# 8_-_Voltage_Conversions_Delays.net
KiCad netlist of a schematic drawn in Altium Designer
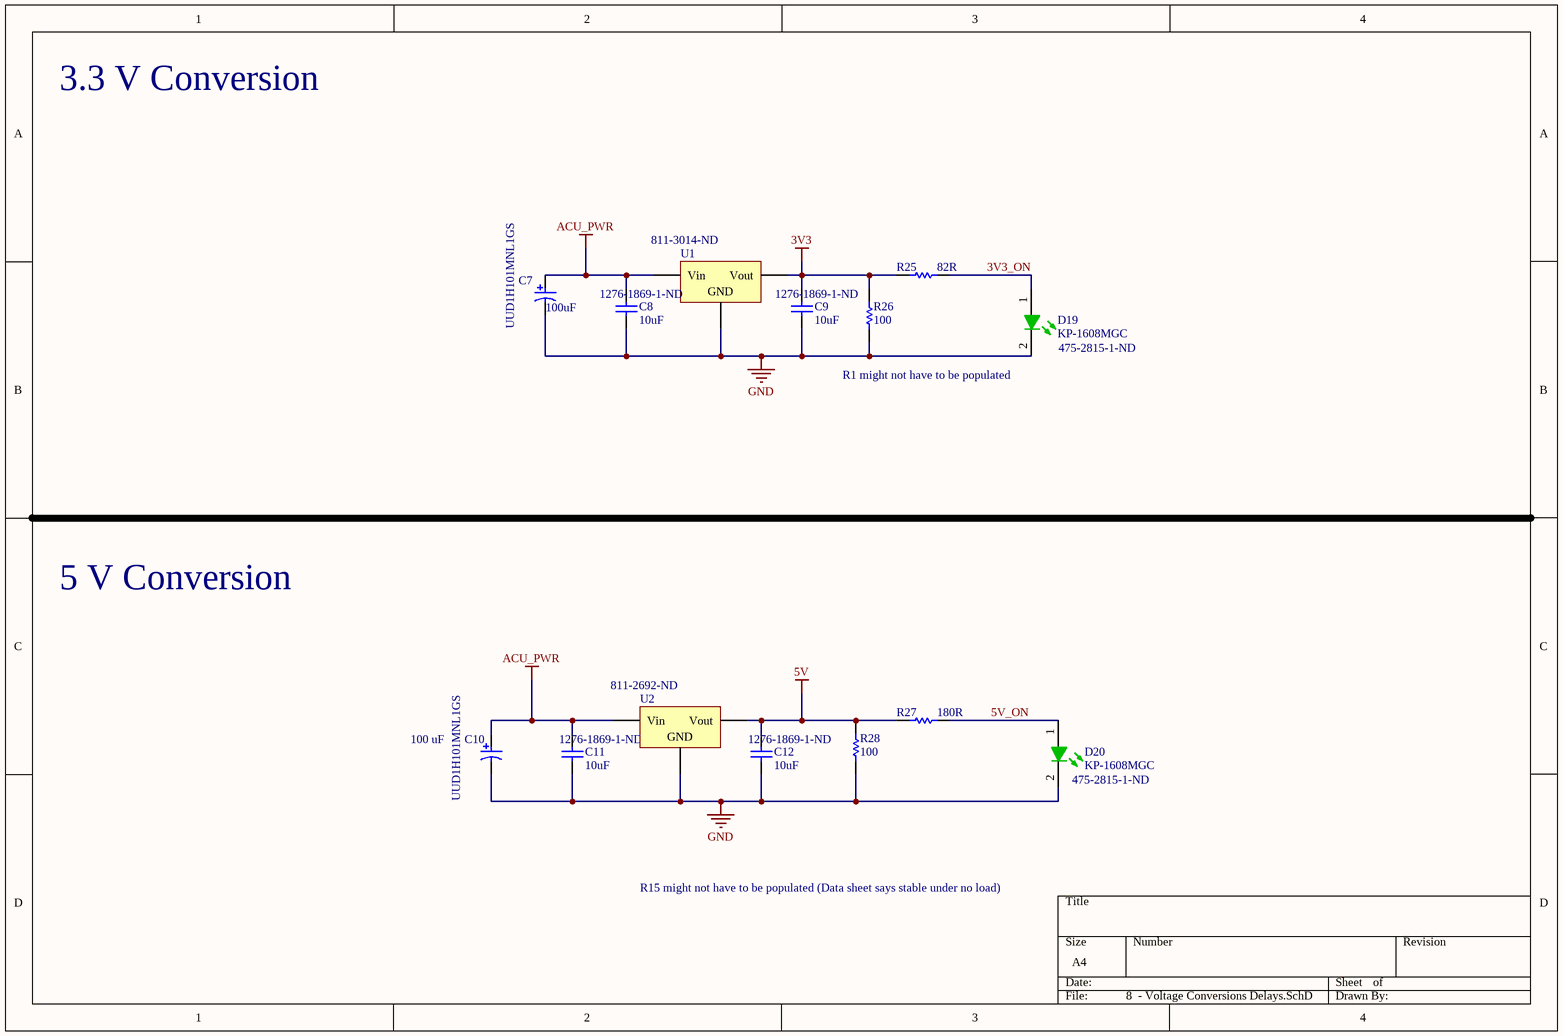
[diagram p0: 8  - Voltage Conversions Delays.SchDoc]

(export (version "E")
  (design (tool "Eeschema 10.0.6"))
  (components
    (comp (ref "C7")
      (value "UUD1H101MNL1GS")
      (footprint "NIC-CAPA2-8X10_V")
      (fields (field (name "MANUFACTURER") "Nichicon") (field (name "TOLERANCE") "±20%"))
      (libsource (lib "Altium Content Vault") (part "CMP-0687-00073-1"))
    )
    (comp (ref "C8")
      (value "10uF")
      (footprint "0603R-generic")
      (description "Capacitor")
      (fields
        (field (name "MANUFACTURER") "Yageo")
        (field (name "MANUFACTURER PART NUMBER") "CC1210ZKY5V8BB106")
        (field (name "SUPPLIER PART NUMBER 2") "1276-1869-1-ND")
      )
      (libsource (lib "Miscellaneous Devices") (part "Cap"))
    )
    (comp (ref "C9")
      (value "10uF")
      (footprint "0603R-generic")
      (description "Capacitor")
      (fields
        (field (name "MANUFACTURER") "Yageo")
        (field (name "MANUFACTURER PART NUMBER") "CC1210ZKY5V8BB106")
        (field (name "SUPPLIER PART NUMBER 2") "1276-1869-1-ND")
      )
      (libsource (lib "Miscellaneous Devices") (part "Cap"))
    )
    (comp (ref "C10")
      (value "UUD1H101MNL1GS")
      (footprint "NIC-CAPA2-8X10_V")
      (fields
        (field (name "MANUFACTURER") "Nichicon")
        (field (name "RATED CAPACITANCE") "100 uF")
        (field (name "TOLERANCE") "±20%")
      )
      (libsource (lib "Altium Content Vault") (part "CMP-0687-00073-1"))
    )
    (comp (ref "C11")
      (value "10uF")
      (footprint "0603R-generic")
      (description "Capacitor")
      (fields
        (field (name "MANUFACTURER") "Yageo")
        (field (name "MANUFACTURER PART NUMBER") "CC1210ZKY5V8BB106")
        (field (name "SUPPLIER PART NUMBER 2") "1276-1869-1-ND")
      )
      (libsource (lib "Miscellaneous Devices") (part "Cap"))
    )
    (comp (ref "C12")
      (value "10uF")
      (footprint "0603R-generic")
      (description "Capacitor")
      (fields
        (field (name "MANUFACTURER") "Yageo")
        (field (name "MANUFACTURER PART NUMBER") "CC1210ZKY5V8BB106")
        (field (name "SUPPLIER PART NUMBER 2") "1276-1869-1-ND")
      )
      (libsource (lib "Miscellaneous Devices") (part "Cap"))
    )
    (comp (ref "D19")
      (value "KP-1608MGC")
      (footprint "KING-0603LED_GREEN_V")
      (description "LED, SMT, 0603(1608), 1.1mm thickness, Green")
      (fields
        (field (name "MANUFACTURER") "Kingbright")
        (field (name "SUPPLIER PART NUMBER 1") "475-2815-1-ND")
      )
      (libsource (lib "Altium Content Vault") (part "KING-LED-GREEN-A1K2-2"))
    )
    (comp (ref "D20")
      (value "KP-1608MGC")
      (footprint "KING-0603LED_GREEN_V")
      (description "LED, SMT, 0603(1608), 1.1mm thickness, Green")
      (fields
        (field (name "MANUFACTURER") "Kingbright")
        (field (name "SUPPLIER PART NUMBER 1") "475-2815-1-ND")
      )
      (libsource (lib "Altium Content Vault") (part "KING-LED-GREEN-A1K2-2"))
    )
    (comp (ref "R25")
      (value "82R")
      (footprint "1608[0603]")
      (description "Resistor")
      (fields
        (field (name "MANUFACTURER") "Yageo")
        (field (name "MANUFACTURER PART NUMBER") "RC0603JR-0782RL")
      )
      (libsource (lib "Miscellaneous Devices") (part "Res1"))
    )
    (comp (ref "R26")
      (value "100")
      (footprint "1608[0603]")
      (description "Resistor")
      (fields
        (field (name "MANUFACTURER") "Yageo")
        (field (name "MANUFACTURER PART NUMBER") "RC0603JR-0782RL")
      )
      (libsource (lib "Miscellaneous Devices") (part "Res1"))
    )
    (comp (ref "R27")
      (value "180R")
      (footprint "1608[0603]")
      (description "Resistor")
      (fields
        (field (name "MANUFACTURER") "Yageo")
        (field (name "MANUFACTURER PART NUMBER") "RC0603JR-07180RL")
      )
      (libsource (lib "Miscellaneous Devices") (part "Res1"))
    )
    (comp (ref "R28")
      (value "100")
      (footprint "1608[0603]")
      (description "Resistor")
      (fields
        (field (name "MANUFACTURER") "Yageo")
        (field (name "MANUFACTURER PART NUMBER") "RC0603JR-0782RL")
      )
      (libsource (lib "Miscellaneous Devices") (part "Res1"))
    )
    (comp (ref "U1")
      (value "Volt Reg")
      (footprint "DCDC_VERTICAL")
      (description "Voltage Regulator")
      (fields
        (field (name "SUPPLIER PART NUMBER 1") "811-3014-ND")
        (field (name "PUBLISHER") "Altium Limited")
      )
      (libsource (lib "Miscellaneous Devices") (part "Volt Reg"))
    )
    (comp (ref "U2")
      (value "Volt Reg")
      (footprint "DCDC_HORIZONTAL")
      (description "Voltage Regulator")
      (fields
        (field (name "SUPPLIER PART NUMBER 1") "811-2692-ND")
        (field (name "PUBLISHER") "Altium Limited")
      )
      (libsource (lib "Miscellaneous Devices") (part "Volt Reg"))
    )
  )
  (nets
    (net (code "1") (name "/3V3_ON") (class "Default")
      (node (ref "D19") (pin "1") (pinfunction "A_1") (pintype "passive"))
      (node (ref "R25") (pin "2") (pinfunction "2_2") (pintype "passive"))
    )
    (net (code "2") (name "/5V_ON") (class "Default")
      (node (ref "D20") (pin "1") (pinfunction "A_1") (pintype "passive"))
      (node (ref "R27") (pin "2") (pinfunction "2_2") (pintype "passive"))
    )
    (net (code "3") (name "3V3") (class "Default")
      (node (ref "C9") (pin "2") (pinfunction "2_2") (pintype "passive"))
      (node (ref "R25") (pin "1") (pinfunction "1_1") (pintype "passive"))
      (node (ref "R26") (pin "2") (pinfunction "2_2") (pintype "passive"))
      (node (ref "U1") (pin "3") (pinfunction "Vout_3") (pintype "passive"))
    )
    (net (code "4") (name "5V") (class "Default")
      (node (ref "C12") (pin "2") (pinfunction "2_2") (pintype "passive"))
      (node (ref "R27") (pin "1") (pinfunction "1_1") (pintype "passive"))
      (node (ref "R28") (pin "2") (pinfunction "2_2") (pintype "passive"))
      (node (ref "U2") (pin "3") (pinfunction "Vout_3") (pintype "passive"))
    )
    (net (code "5") (name "ACU_PWR") (class "Default")
      (node (ref "C10") (pin "1") (pinfunction "1_1") (pintype "passive"))
      (node (ref "C11") (pin "2") (pinfunction "2_2") (pintype "passive"))
      (node (ref "C7") (pin "1") (pinfunction "1_1") (pintype "passive"))
      (node (ref "C8") (pin "2") (pinfunction "2_2") (pintype "passive"))
      (node (ref "U1") (pin "1") (pinfunction "Vin_1") (pintype "passive"))
      (node (ref "U2") (pin "1") (pinfunction "Vin_1") (pintype "passive"))
    )
    (net (code "6") (name "GND") (class "Default")
      (node (ref "C10") (pin "2") (pinfunction "2_2") (pintype "passive"))
      (node (ref "C11") (pin "1") (pinfunction "1_1") (pintype "passive"))
      (node (ref "C12") (pin "1") (pinfunction "1_1") (pintype "passive"))
      (node (ref "C7") (pin "2") (pinfunction "2_2") (pintype "passive"))
      (node (ref "C8") (pin "1") (pinfunction "1_1") (pintype "passive"))
      (node (ref "C9") (pin "1") (pinfunction "1_1") (pintype "passive"))
      (node (ref "D19") (pin "2") (pinfunction "K_2") (pintype "passive"))
      (node (ref "D20") (pin "2") (pinfunction "K_2") (pintype "passive"))
      (node (ref "R26") (pin "1") (pinfunction "1_1") (pintype "passive"))
      (node (ref "R28") (pin "1") (pinfunction "1_1") (pintype "passive"))
      (node (ref "U1") (pin "2") (pinfunction "GND_2") (pintype "passive"))
      (node (ref "U2") (pin "2") (pinfunction "GND_2") (pintype "passive"))
    )
  )
)
